# iSOLATED_RS485.net
KiCad netlist of a schematic drawn in Altium Designer
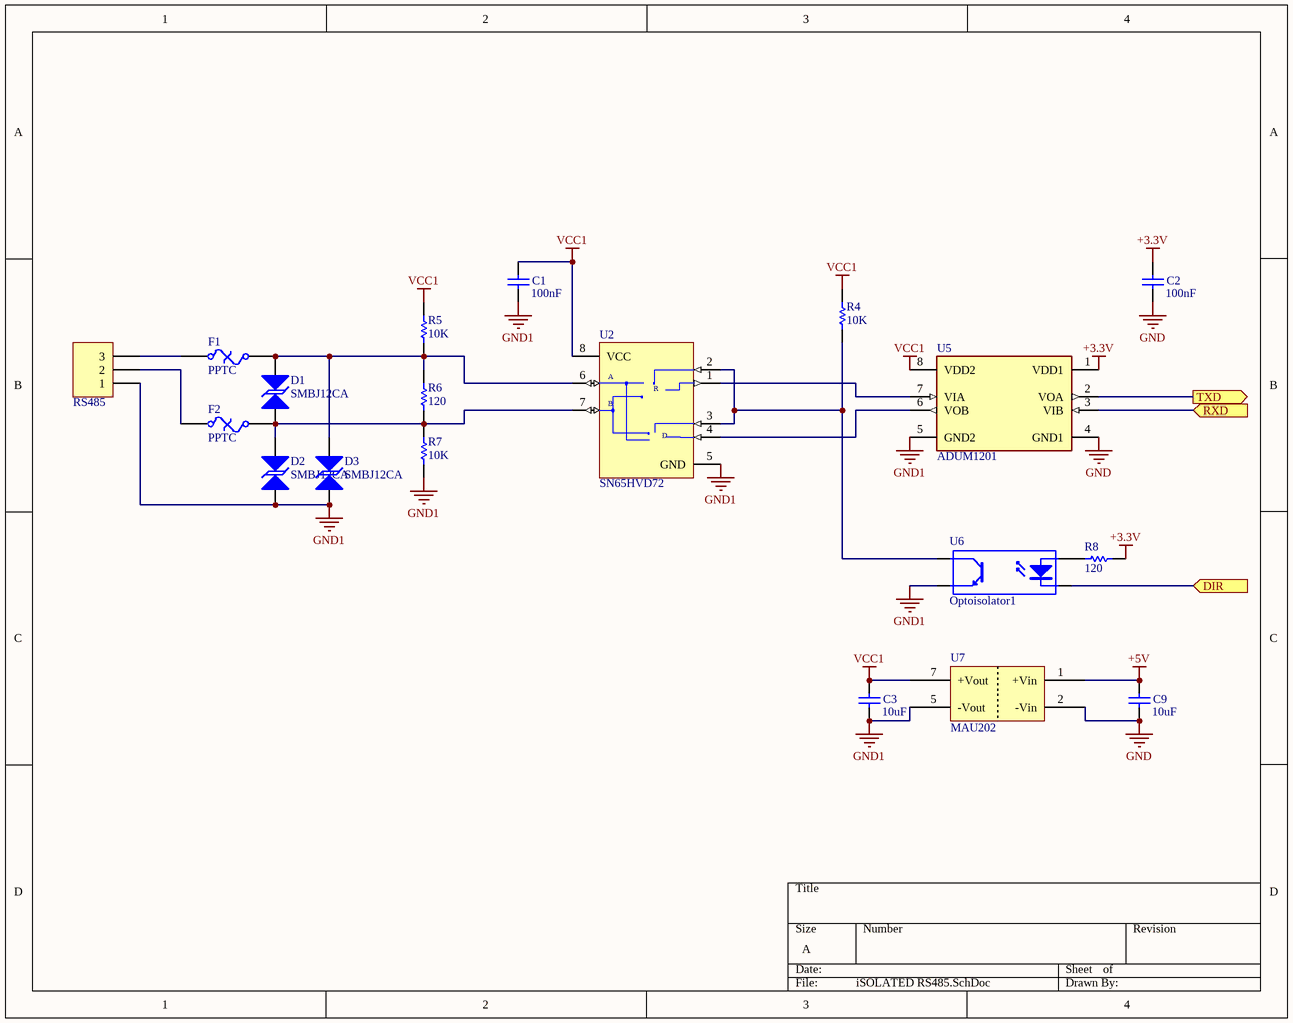
[diagram p0: iSOLATED RS485.SchDoc]

(export (version "E")
  (design (tool "Eeschema 10.0.6"))
  (components
    (comp (ref "C1")
      (value "100nF")
      (footprint "C603")
      (description "Capacitor")
      (fields (field (name "DESIGNER") "Parsa Malekpour"))
      (libsource (lib "UserPKG") (part "Cap"))
    )
    (comp (ref "C2")
      (value "100nF")
      (footprint "C603")
      (description "Capacitor")
      (fields (field (name "DESIGNER") "Parsa Malekpour"))
      (libsource (lib "UserPKG") (part "Cap"))
    )
    (comp (ref "C3")
      (value "10uF")
      (footprint "C1206")
      (description "Capacitor")
      (fields (field (name "DESIGNER") "Parsa Malekpour"))
      (libsource (lib "UserPKG") (part "Cap"))
    )
    (comp (ref "C9")
      (value "10uF")
      (footprint "C1206")
      (description "Capacitor")
      (fields (field (name "DESIGNER") "Parsa Malekpour"))
      (libsource (lib "UserPKG") (part "Cap"))
    )
    (comp (ref "D1")
      (value "SMBJ12CA")
      (footprint "DO-214AA")
      (description "Surface Mount Transient Voltage Suppressors Diode")
      (libsource (lib "ParsaLibrary") (part "SMBJxxCA"))
    )
    (comp (ref "D2")
      (value "SMBJ12CA")
      (footprint "DO-214AA")
      (description "Surface Mount Transient Voltage Suppressors Diode")
      (libsource (lib "ParsaLibrary") (part "SMBJxxCA"))
    )
    (comp (ref "D3")
      (value "SMBJ12CA")
      (footprint "DO-214AA")
      (description "Surface Mount Transient Voltage Suppressors Diode")
      (libsource (lib "ParsaLibrary") (part "SMBJxxCA"))
    )
    (comp (ref "F1")
      (value "PPTC")
      (footprint "PTC-0805")
      (description "Thermal Fuse")
      (fields (field (name "PUBLISHER") "Altium Limited"))
      (libsource (lib "Miscellaneous Devices") (part "Fuse Thermal"))
    )
    (comp (ref "F2")
      (value "PPTC")
      (footprint "PTC-0805")
      (description "Thermal Fuse")
      (fields (field (name "PUBLISHER") "Altium Limited"))
      (libsource (lib "Miscellaneous Devices") (part "Fuse Thermal"))
    )
    (comp (ref "R4")
      (value "10K")
      (footprint "R805")
      (description "Resistor")
      (fields (field (name "DESIGNER") "Parsa Malekpour"))
      (libsource (lib "ParsaLibrary") (part "Resistor"))
    )
    (comp (ref "R5")
      (value "10K")
      (footprint "R805")
      (description "Resistor")
      (fields (field (name "DESIGNER") "Parsa Malekpour"))
      (libsource (lib "ParsaLibrary") (part "Resistor"))
    )
    (comp (ref "R6")
      (value "120")
      (footprint "R805")
      (description "Resistor")
      (fields (field (name "DESIGNER") "Parsa Malekpour"))
      (libsource (lib "ParsaLibrary") (part "Resistor"))
    )
    (comp (ref "R7")
      (value "10K")
      (footprint "R805")
      (description "Resistor")
      (fields (field (name "DESIGNER") "Parsa Malekpour"))
      (libsource (lib "ParsaLibrary") (part "Resistor"))
    )
    (comp (ref "R8")
      (value "120")
      (footprint "R805")
      (description "Resistor")
      (fields (field (name "DESIGNER") "Parsa Malekpour"))
      (libsource (lib "ParsaLibrary") (part "Resistor"))
    )
    (comp (ref "RS485")
      (value "CONN-3")
      (footprint "XH-3")
      (description "Header, 3-Pin")
      (libsource (lib "ParsaLibrary") (part "CONN-3"))
    )
    (comp (ref "U2")
      (value "SN65HVD72")
      (footprint "SOIC-8N")
      (description "3.3-V Supply RS-485 With IEC ESD protection")
      (fields (field (name "PUBLISHER") "Altium Limited"))
      (libsource (lib "ParsaLibrary") (part "SN65HVD72"))
    )
    (comp (ref "U5")
      (value "ADUM1201")
      (footprint "soic-8n")
      (description "Dual-Channel Digital Isolators")
      (fields (field (name "MF") "{'manufacturer': u'Analog Devices'}") (field (name "MP") "ADUM1201AR"))
      (libsource (lib "ParsaLibrary") (part "ADUM1201"))
    )
    (comp (ref "U6")
      (value "Optoisolator1")
      (footprint "SOIC-4")
      (description "4-Pin Phototransistor Optocoupler")
      (fields (field (name "PUBLISHER") "Altium Limited"))
      (libsource (lib "Miscellaneous Devices") (part "Optoisolator1"))
    )
    (comp (ref "U7")
      (value "MAU202")
      (footprint "MAU202")
      (description "1W, FIXED INPUT ISOLATED & UNREGULATED\r\nSINGLE OUTPUT DC-DC CONVERTER")
      (libsource (lib "ParsaLibrary") (part "MAU202"))
    )
  )
  (nets
    (net (code "1") (name "+3.3V") (class "Default")
      (node (ref "C2") (pin "2") (pinfunction "2_2") (pintype "passive"))
      (node (ref "R8") (pin "1") (pinfunction "1_1") (pintype "passive"))
      (node (ref "U5") (pin "1") (pinfunction "VDD1_1") (pintype "power_in"))
    )
    (net (code "2") (name "+5V") (class "Default")
      (node (ref "C9") (pin "2") (pinfunction "2_2") (pintype "passive"))
      (node (ref "U7") (pin "1") (pinfunction "+Vin_1") (pintype "passive"))
    )
    (net (code "3") (name "/DIR") (class "Default")
      (node (ref "U6") (pin "2") (pinfunction "K_2") (pintype "passive"))
    )
    (net (code "4") (name "/RXD") (class "Default")
      (node (ref "U5") (pin "3") (pinfunction "VIB_3") (pintype "input"))
    )
    (net (code "5") (name "/TXD") (class "Default")
      (node (ref "U5") (pin "2") (pinfunction "VOA_2") (pintype "output"))
    )
    (net (code "6") (name "GND") (class "Default")
      (node (ref "C2") (pin "1") (pinfunction "1_1") (pintype "passive"))
      (node (ref "C9") (pin "1") (pinfunction "1_1") (pintype "passive"))
      (node (ref "U5") (pin "4") (pinfunction "GND1_4") (pintype "passive"))
      (node (ref "U7") (pin "2") (pinfunction "-Vin_2") (pintype "passive"))
    )
    (net (code "7") (name "GND1") (class "Default")
      (node (ref "C1") (pin "1") (pinfunction "1_1") (pintype "passive"))
      (node (ref "C3") (pin "1") (pinfunction "1_1") (pintype "passive"))
      (node (ref "D2") (pin "1") (pinfunction "A_1") (pintype "passive"))
      (node (ref "D3") (pin "1") (pinfunction "A_1") (pintype "passive"))
      (node (ref "R7") (pin "1") (pinfunction "1_1") (pintype "passive"))
      (node (ref "RS485") (pin "1") (pinfunction "1_1") (pintype "passive"))
      (node (ref "U2") (pin "5") (pinfunction "GND_5") (pintype "power_in"))
      (node (ref "U5") (pin "5") (pinfunction "GND2_5") (pintype "passive"))
      (node (ref "U6") (pin "3") (pinfunction "E_3") (pintype "passive"))
      (node (ref "U7") (pin "5") (pinfunction "-Vout_5") (pintype "passive"))
    )
    (net (code "8") (name "Net-(D1-A)") (class "Default")
      (node (ref "D1") (pin "1") (pinfunction "A_1") (pintype "passive"))
      (node (ref "D2") (pin "2") (pinfunction "K_2") (pintype "passive"))
      (node (ref "F2") (pin "2") (pinfunction "2_2") (pintype "passive"))
      (node (ref "R6") (pin "1") (pinfunction "1_1") (pintype "passive"))
      (node (ref "R7") (pin "2") (pinfunction "2_2") (pintype "passive"))
      (node (ref "U2") (pin "7") (pinfunction "B_7") (pintype "bidirectional"))
    )
    (net (code "9") (name "Net-(D1-K)") (class "Default")
      (node (ref "D1") (pin "2") (pinfunction "K_2") (pintype "passive"))
      (node (ref "D3") (pin "2") (pinfunction "K_2") (pintype "passive"))
      (node (ref "F1") (pin "2") (pinfunction "2_2") (pintype "passive"))
      (node (ref "R5") (pin "1") (pinfunction "1_1") (pintype "passive"))
      (node (ref "R6") (pin "2") (pinfunction "2_2") (pintype "passive"))
      (node (ref "U2") (pin "6") (pinfunction "A_6") (pintype "bidirectional"))
    )
    (net (code "10") (name "Net-(F1-Pad1)") (class "Default")
      (node (ref "F1") (pin "1") (pinfunction "1_1") (pintype "passive"))
      (node (ref "RS485") (pin "3") (pinfunction "3_3") (pintype "passive"))
    )
    (net (code "11") (name "Net-(F2-Pad1)") (class "Default")
      (node (ref "F2") (pin "1") (pinfunction "1_1") (pintype "passive"))
      (node (ref "RS485") (pin "2") (pinfunction "2_2") (pintype "passive"))
    )
    (net (code "12") (name "Net-(U2-DE)") (class "Default")
      (node (ref "R4") (pin "1") (pinfunction "1_1") (pintype "passive"))
      (node (ref "U2") (pin "2") (pinfunction "~{RE}_2") (pintype "input"))
      (node (ref "U2") (pin "3") (pinfunction "DE_3") (pintype "input"))
      (node (ref "U6") (pin "4") (pinfunction "C_4") (pintype "passive"))
    )
    (net (code "13") (name "Net-(U2-DI)") (class "Default")
      (node (ref "U2") (pin "4") (pinfunction "DI_4") (pintype "input"))
      (node (ref "U5") (pin "6") (pinfunction "VOB_6") (pintype "output"))
    )
    (net (code "14") (name "Net-(U2-RO)") (class "Default")
      (node (ref "U2") (pin "1") (pinfunction "RO_1") (pintype "output"))
      (node (ref "U5") (pin "7") (pinfunction "VIA_7") (pintype "input"))
    )
    (net (code "15") (name "Net-(U6-A)") (class "Default")
      (node (ref "R8") (pin "2") (pinfunction "2_2") (pintype "passive"))
      (node (ref "U6") (pin "1") (pinfunction "A_1") (pintype "passive"))
    )
    (net (code "16") (name "VCC1") (class "Default")
      (node (ref "C1") (pin "2") (pinfunction "2_2") (pintype "passive"))
      (node (ref "C3") (pin "2") (pinfunction "2_2") (pintype "passive"))
      (node (ref "R4") (pin "2") (pinfunction "2_2") (pintype "passive"))
      (node (ref "R5") (pin "2") (pinfunction "2_2") (pintype "passive"))
      (node (ref "U2") (pin "8") (pinfunction "VCC_8") (pintype "power_in"))
      (node (ref "U5") (pin "8") (pinfunction "VDD2_8") (pintype "power_in"))
      (node (ref "U7") (pin "7") (pinfunction "+Vout_7") (pintype "passive"))
    )
  )
)
